# Stepper_Driver_jig_bottom.net
KiCad netlist of a schematic drawn in EAGLE
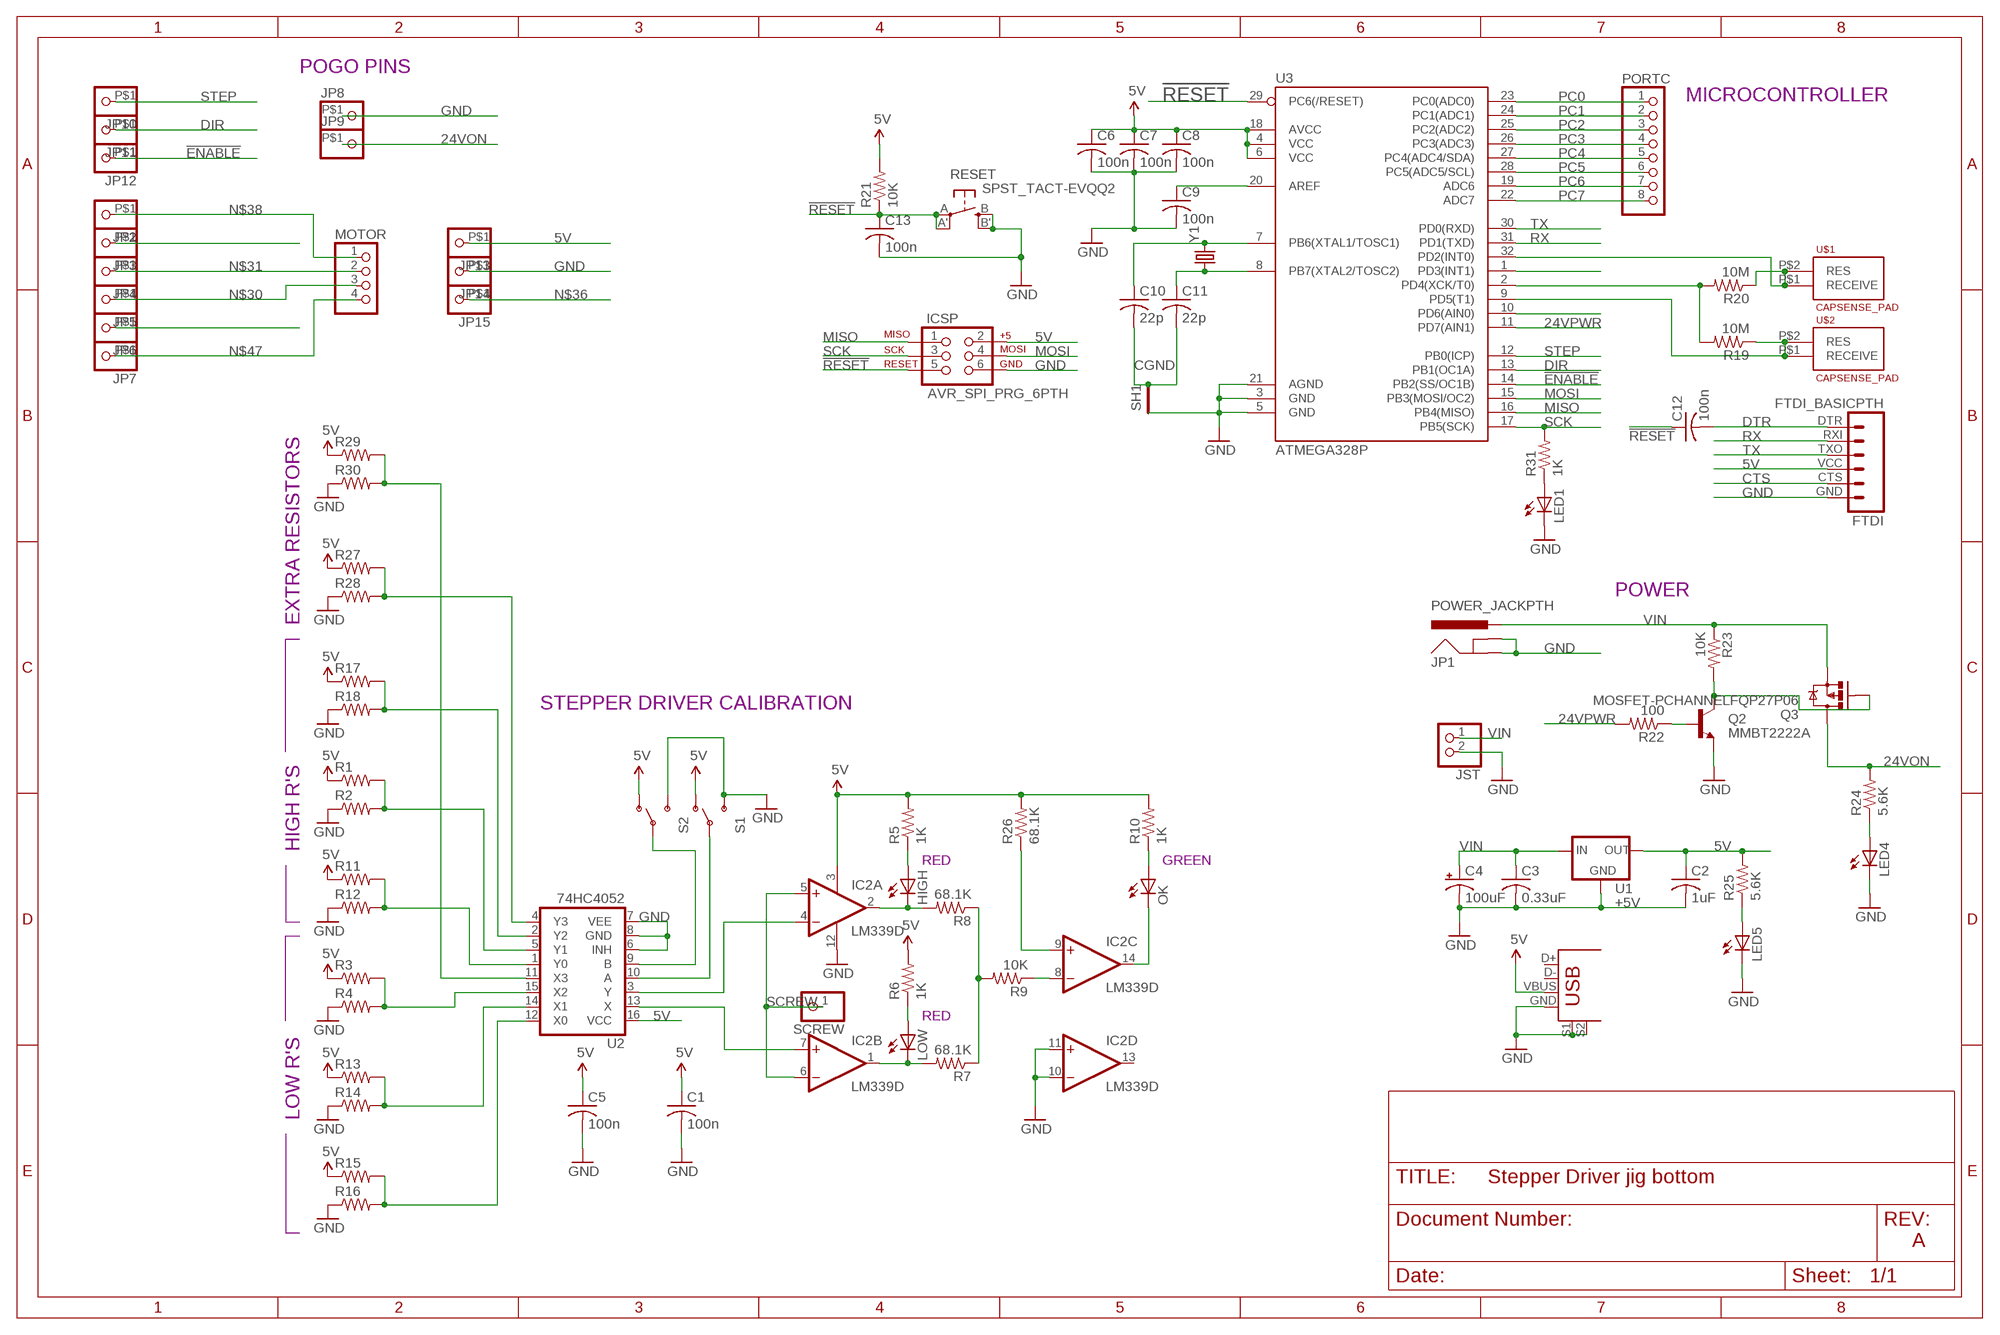
[diagram p0: schematic, sheet 1]

(export (version "E")
  (design (tool "Eeschema 10.0.6"))
  (components
    (comp (ref "C1")
      (value "100n")
      (footprint "eagle-import:C0805")
      (libsource (lib "eagle-import") (part "C-USC0805"))
    )
    (comp (ref "C2")
      (value "1uF")
      (footprint "eagle-import:C0805")
      (libsource (lib "eagle-import") (part "C-USC0805"))
    )
    (comp (ref "C3")
      (value "0.33uF")
      (footprint "eagle-import:C0805")
      (libsource (lib "eagle-import") (part "C-USC0805"))
    )
    (comp (ref "C4")
      (value "100uF")
      (footprint "eagle-import:UD-8X10_NICHICON")
      (libsource (lib "eagle-import") (part "CPOL-USUD-8X10"))
    )
    (comp (ref "C5")
      (value "100n")
      (footprint "eagle-import:C0805")
      (libsource (lib "eagle-import") (part "C-USC0805"))
    )
    (comp (ref "C6")
      (value "100n")
      (footprint "eagle-import:C0805")
      (libsource (lib "eagle-import") (part "C-USC0805"))
    )
    (comp (ref "C7")
      (value "100n")
      (footprint "eagle-import:C0805")
      (libsource (lib "eagle-import") (part "C-USC0805"))
    )
    (comp (ref "C8")
      (value "100n")
      (footprint "eagle-import:C0805")
      (libsource (lib "eagle-import") (part "C-USC0805"))
    )
    (comp (ref "C9")
      (value "100n")
      (footprint "eagle-import:C0805")
      (libsource (lib "eagle-import") (part "C-USC0805"))
    )
    (comp (ref "C10")
      (value "22p")
      (footprint "eagle-import:C0805")
      (libsource (lib "eagle-import") (part "C-USC0805"))
    )
    (comp (ref "C11")
      (value "22p")
      (footprint "eagle-import:C0805")
      (libsource (lib "eagle-import") (part "C-USC0805"))
    )
    (comp (ref "C12")
      (value "100n")
      (footprint "eagle-import:C0805")
      (libsource (lib "eagle-import") (part "C-USC0805"))
    )
    (comp (ref "C13")
      (value "100n")
      (footprint "eagle-import:C0805")
      (libsource (lib "eagle-import") (part "C-USC0805"))
    )
    (comp (ref "FTDI")
      (value "FTDI_BASICPTH")
      (footprint "eagle-import:FTDI_BASIC")
      (libsource (lib "eagle-import") (part "FTDI_BASICPTH"))
    )
    (comp (ref "HIGH")
      (value "LEDCHIPLED_1206")
      (footprint "eagle-import:CHIPLED_1206")
      (libsource (lib "eagle-import") (part "LEDCHIPLED_1206"))
    )
    (comp (ref "IC2")
      (value "LM339D")
      (footprint "eagle-import:SO14")
      (libsource (lib "eagle-import") (part "LM339D"))
    )
    (comp (ref "ICSP")
      (value "AVR_SPI_PRG_6PTH")
      (footprint "eagle-import:2X3")
      (libsource (lib "eagle-import") (part "AVR_SPI_PRG_6PTH"))
    )
    (comp (ref "JP1")
      (value "POWER_JACKPTH")
      (footprint "eagle-import:POWER_JACK_PTH")
      (libsource (lib "eagle-import") (part "POWER_JACKPTH"))
    )
    (comp (ref "JP2")
      (value "PINHD-1X1")
      (footprint "eagle-import:POGOPIN")
      (libsource (lib "eagle-import") (part "PINHD-1X1"))
    )
    (comp (ref "JP3")
      (value "PINHD-1X1")
      (footprint "eagle-import:POGOPIN")
      (libsource (lib "eagle-import") (part "PINHD-1X1"))
    )
    (comp (ref "JP4")
      (value "PINHD-1X1")
      (footprint "eagle-import:POGOPIN")
      (libsource (lib "eagle-import") (part "PINHD-1X1"))
    )
    (comp (ref "JP5")
      (value "PINHD-1X1")
      (footprint "eagle-import:POGOPIN")
      (libsource (lib "eagle-import") (part "PINHD-1X1"))
    )
    (comp (ref "JP6")
      (value "PINHD-1X1")
      (footprint "eagle-import:POGOPIN")
      (libsource (lib "eagle-import") (part "PINHD-1X1"))
    )
    (comp (ref "JP7")
      (value "PINHD-1X1")
      (footprint "eagle-import:POGOPIN")
      (libsource (lib "eagle-import") (part "PINHD-1X1"))
    )
    (comp (ref "JP8")
      (value "PINHD-1X1")
      (footprint "eagle-import:POGOPIN")
      (libsource (lib "eagle-import") (part "PINHD-1X1"))
    )
    (comp (ref "JP9")
      (value "PINHD-1X1")
      (footprint "eagle-import:POGOPIN")
      (libsource (lib "eagle-import") (part "PINHD-1X1"))
    )
    (comp (ref "JP10")
      (value "PINHD-1X1")
      (footprint "eagle-import:POGOPIN")
      (libsource (lib "eagle-import") (part "PINHD-1X1"))
    )
    (comp (ref "JP11")
      (value "PINHD-1X1")
      (footprint "eagle-import:POGOPIN")
      (libsource (lib "eagle-import") (part "PINHD-1X1"))
    )
    (comp (ref "JP12")
      (value "PINHD-1X1")
      (footprint "eagle-import:POGOPIN")
      (libsource (lib "eagle-import") (part "PINHD-1X1"))
    )
    (comp (ref "JP13")
      (value "PINHD-1X1")
      (footprint "eagle-import:POGOPIN")
      (libsource (lib "eagle-import") (part "PINHD-1X1"))
    )
    (comp (ref "JP14")
      (value "PINHD-1X1")
      (footprint "eagle-import:POGOPIN")
      (libsource (lib "eagle-import") (part "PINHD-1X1"))
    )
    (comp (ref "JP15")
      (value "PINHD-1X1")
      (footprint "eagle-import:POGOPIN")
      (libsource (lib "eagle-import") (part "PINHD-1X1"))
    )
    (comp (ref "JST")
      (value "JST_2PIN-SMT-RA")
      (footprint "eagle-import:JST-PH-2-SMT-RA")
      (libsource (lib "eagle-import") (part "JST_2PIN-SMT-RA"))
    )
    (comp (ref "LED1")
      (value "LEDCHIP-LED0805")
      (footprint "eagle-import:CHIP-LED0805")
      (libsource (lib "eagle-import") (part "LEDCHIP-LED0805"))
    )
    (comp (ref "LED4")
      (value "LEDCHIPLED_0805")
      (footprint "eagle-import:CHIPLED_0805")
      (libsource (lib "eagle-import") (part "LEDCHIPLED_0805"))
    )
    (comp (ref "LED5")
      (value "LEDCHIPLED_0805")
      (footprint "eagle-import:CHIPLED_0805")
      (libsource (lib "eagle-import") (part "LEDCHIPLED_0805"))
    )
    (comp (ref "LOW")
      (value "LEDCHIPLED_1206")
      (footprint "eagle-import:CHIPLED_1206")
      (libsource (lib "eagle-import") (part "LEDCHIPLED_1206"))
    )
    (comp (ref "MOTOR")
      (value "PINHD-1X4")
      (footprint "eagle-import:1X04")
      (libsource (lib "eagle-import") (part "PINHD-1X4"))
    )
    (comp (ref "OK")
      (value "LEDCHIPLED_1206")
      (footprint "eagle-import:CHIPLED_1206")
      (libsource (lib "eagle-import") (part "LEDCHIPLED_1206"))
    )
    (comp (ref "PORTC")
      (value "PINHD-1X8")
      (footprint "eagle-import:1X08")
      (libsource (lib "eagle-import") (part "PINHD-1X8"))
    )
    (comp (ref "Q2")
      (value "MMBT2222A")
      (footprint "eagle-import:SOT23-3")
      (libsource (lib "eagle-import") (part "TRANSISTOR_NPNMMBT2222A"))
    )
    (comp (ref "Q3")
      (value "MOSFET-PCHANNELFQP27P06")
      (footprint "eagle-import:TO220V")
      (libsource (lib "eagle-import") (part "MOSFET-PCHANNELFQP27P06"))
    )
    (comp (ref "R1")
      (value "R-US_M0805")
      (footprint "eagle-import:M0805")
      (libsource (lib "eagle-import") (part "R-US_M0805"))
    )
    (comp (ref "R2")
      (value "R-US_M0805")
      (footprint "eagle-import:M0805")
      (libsource (lib "eagle-import") (part "R-US_M0805"))
    )
    (comp (ref "R3")
      (value "R-US_M0805")
      (footprint "eagle-import:M0805")
      (libsource (lib "eagle-import") (part "R-US_M0805"))
    )
    (comp (ref "R4")
      (value "R-US_M0805")
      (footprint "eagle-import:M0805")
      (libsource (lib "eagle-import") (part "R-US_M0805"))
    )
    (comp (ref "R5")
      (value "1K")
      (footprint "eagle-import:M0805")
      (libsource (lib "eagle-import") (part "R-US_M0805"))
    )
    (comp (ref "R6")
      (value "1K")
      (footprint "eagle-import:M0805")
      (libsource (lib "eagle-import") (part "R-US_M0805"))
    )
    (comp (ref "R7")
      (value "68.1K")
      (footprint "eagle-import:M0805")
      (libsource (lib "eagle-import") (part "R-US_M0805"))
    )
    (comp (ref "R8")
      (value "68.1K")
      (footprint "eagle-import:M0805")
      (libsource (lib "eagle-import") (part "R-US_M0805"))
    )
    (comp (ref "R9")
      (value "10K")
      (footprint "eagle-import:M0805")
      (libsource (lib "eagle-import") (part "R-US_M0805"))
    )
    (comp (ref "R10")
      (value "1K")
      (footprint "eagle-import:M0805")
      (libsource (lib "eagle-import") (part "R-US_M0805"))
    )
    (comp (ref "R11")
      (value "R-US_M0805")
      (footprint "eagle-import:M0805")
      (libsource (lib "eagle-import") (part "R-US_M0805"))
    )
    (comp (ref "R12")
      (value "R-US_M0805")
      (footprint "eagle-import:M0805")
      (libsource (lib "eagle-import") (part "R-US_M0805"))
    )
    (comp (ref "R13")
      (value "R-US_M0805")
      (footprint "eagle-import:M0805")
      (libsource (lib "eagle-import") (part "R-US_M0805"))
    )
    (comp (ref "R14")
      (value "R-US_M0805")
      (footprint "eagle-import:M0805")
      (libsource (lib "eagle-import") (part "R-US_M0805"))
    )
    (comp (ref "R15")
      (value "R-US_M0805")
      (footprint "eagle-import:M0805")
      (libsource (lib "eagle-import") (part "R-US_M0805"))
    )
    (comp (ref "R16")
      (value "R-US_M0805")
      (footprint "eagle-import:M0805")
      (libsource (lib "eagle-import") (part "R-US_M0805"))
    )
    (comp (ref "R17")
      (value "R-US_M0805")
      (footprint "eagle-import:M0805")
      (libsource (lib "eagle-import") (part "R-US_M0805"))
    )
    (comp (ref "R18")
      (value "R-US_M0805")
      (footprint "eagle-import:M0805")
      (libsource (lib "eagle-import") (part "R-US_M0805"))
    )
    (comp (ref "R19")
      (value "10M")
      (footprint "eagle-import:M0805")
      (libsource (lib "eagle-import") (part "R-US_M0805"))
    )
    (comp (ref "R20")
      (value "10M")
      (footprint "eagle-import:M0805")
      (libsource (lib "eagle-import") (part "R-US_M0805"))
    )
    (comp (ref "R21")
      (value "10K")
      (footprint "eagle-import:M0805")
      (libsource (lib "eagle-import") (part "R-US_M0805"))
    )
    (comp (ref "R22")
      (value "100")
      (footprint "eagle-import:M0805")
      (libsource (lib "eagle-import") (part "R-US_M0805"))
    )
    (comp (ref "R23")
      (value "10K")
      (footprint "eagle-import:M0805")
      (libsource (lib "eagle-import") (part "R-US_M0805"))
    )
    (comp (ref "R24")
      (value "5.6K")
      (footprint "eagle-import:M0805")
      (libsource (lib "eagle-import") (part "R-US_M0805"))
    )
    (comp (ref "R25")
      (value "5.6K")
      (footprint "eagle-import:M0805")
      (libsource (lib "eagle-import") (part "R-US_M0805"))
    )
    (comp (ref "R26")
      (value "68.1K")
      (footprint "eagle-import:M0805")
      (libsource (lib "eagle-import") (part "R-US_M0805"))
    )
    (comp (ref "R27")
      (value "R-US_M0805")
      (footprint "eagle-import:M0805")
      (libsource (lib "eagle-import") (part "R-US_M0805"))
    )
    (comp (ref "R28")
      (value "R-US_M0805")
      (footprint "eagle-import:M0805")
      (libsource (lib "eagle-import") (part "R-US_M0805"))
    )
    (comp (ref "R29")
      (value "R-US_M0805")
      (footprint "eagle-import:M0805")
      (libsource (lib "eagle-import") (part "R-US_M0805"))
    )
    (comp (ref "R30")
      (value "R-US_M0805")
      (footprint "eagle-import:M0805")
      (libsource (lib "eagle-import") (part "R-US_M0805"))
    )
    (comp (ref "R31")
      (value "1K")
      (footprint "eagle-import:M0805")
      (libsource (lib "eagle-import") (part "R-US_M0805"))
    )
    (comp (ref "RESET")
      (value "SPST_TACT-EVQQ2")
      (footprint "eagle-import:EVQ-Q2")
      (libsource (lib "eagle-import") (part "SPST_TACT-EVQQ2"))
    )
    (comp (ref "S1")
      (value "SWITCH-SPDTKIT")
      (footprint "eagle-import:SWITCH-SPDT_KIT")
      (libsource (lib "eagle-import") (part "SWITCH-SPDTKIT"))
    )
    (comp (ref "S2")
      (value "SWITCH-SPDTKIT")
      (footprint "eagle-import:SWITCH-SPDT_KIT")
      (libsource (lib "eagle-import") (part "SWITCH-SPDTKIT"))
    )
    (comp (ref "SCREW")
      (value "PINHD-1X1")
      (footprint "eagle-import:1X01")
      (libsource (lib "eagle-import") (part "pinhead_PINHD-1X1"))
    )
    (comp (ref "SH1")
      (value "SHORTT5")
      (footprint "eagle-import:SHORT_TOP-50")
      (libsource (lib "eagle-import") (part "SHORTT5"))
    )
    (comp (ref "U$1")
      (value "CAPSENSE_PAD")
      (footprint "eagle-import:CAPSENSE_PAD")
      (libsource (lib "eagle-import") (part "CAPSENSE_PAD"))
    )
    (comp (ref "U$2")
      (value "CAPSENSE_PAD")
      (footprint "eagle-import:CAPSENSE_PAD")
      (libsource (lib "eagle-import") (part "CAPSENSE_PAD"))
    )
    (comp (ref "U$3")
      (value "USB+SHIELD")
      (footprint "eagle-import:USB-B-PTH")
      (libsource (lib "eagle-import") (part "USB+SHIELD"))
    )
    (comp (ref "U1")
      (value "+5V")
      (footprint "eagle-import:TO-252")
      (libsource (lib "eagle-import") (part "V_REG_78XX7812"))
    )
    (comp (ref "U2")
      (value "74HC4052")
      (footprint "eagle-import:SO16")
      (libsource (lib "eagle-import") (part "74HC4052SO"))
    )
    (comp (ref "U3")
      (value "ATMEGA328P")
      (footprint "eagle-import:TQFP32-08")
      (libsource (lib "eagle-import") (part "ATMEGA328P_TQFP"))
    )
    (comp (ref "Y1")
      (value "CRYSTALHC49US")
      (footprint "eagle-import:HC49US")
      (libsource (lib "eagle-import") (part "CRYSTALHC49US"))
    )
  )
  (nets
    (net (code "1") (name "/24VON") (class "Default")
      (node (ref "JP9") (pin "P$1") (pinfunction "1_P$1") (pintype "passive"))
      (node (ref "Q3") (pin "2") (pinfunction "D_2") (pintype "passive"))
      (node (ref "R24") (pin "2") (pinfunction "2_2") (pintype "passive"))
    )
    (net (code "2") (name "/24VPWR") (class "Default")
      (node (ref "R22") (pin "2") (pinfunction "2_2") (pintype "passive"))
      (node (ref "U3") (pin "11") (pinfunction "PD7(AIN1)_11") (pintype "bidirectional"))
    )
    (net (code "3") (name "/CGND") (class "Default")
      (node (ref "C10") (pin "2") (pinfunction "2_2") (pintype "passive"))
      (node (ref "C11") (pin "2") (pinfunction "2_2") (pintype "passive"))
      (node (ref "SH1") (pin "2") (pinfunction "P$2_2") (pintype "bidirectional"))
    )
    (net (code "4") (name "/CTS") (class "Default")
      (node (ref "FTDI") (pin "CTS") (pinfunction "5_CTS") (pintype "passive"))
    )
    (net (code "5") (name "/DIR") (class "Default")
      (node (ref "JP11") (pin "P$1") (pinfunction "1_P$1") (pintype "passive"))
      (node (ref "U3") (pin "13") (pinfunction "PB1(OC1A)_13") (pintype "bidirectional"))
    )
    (net (code "6") (name "/DTR") (class "Default")
      (node (ref "C12") (pin "2") (pinfunction "2_2") (pintype "passive"))
      (node (ref "FTDI") (pin "DTR") (pinfunction "1_DTR") (pintype "passive"))
    )
    (net (code "7") (name "/MISO") (class "Default")
      (node (ref "ICSP") (pin "1") (pinfunction "1_1") (pintype "passive"))
      (node (ref "U3") (pin "16") (pinfunction "PB4(MISO)_16") (pintype "bidirectional"))
    )
    (net (code "8") (name "/MOSI") (class "Default")
      (node (ref "ICSP") (pin "4") (pinfunction "4_4") (pintype "passive"))
      (node (ref "U3") (pin "15") (pinfunction "PB3(MOSI/OC2)_15") (pintype "bidirectional"))
    )
    (net (code "9") (name "/N$30") (class "Default")
      (node (ref "JP5") (pin "P$1") (pinfunction "1_P$1") (pintype "passive"))
      (node (ref "MOTOR") (pin "3") (pinfunction "3_3") (pintype "passive"))
    )
    (net (code "10") (name "/N$31") (class "Default")
      (node (ref "JP4") (pin "P$1") (pinfunction "1_P$1") (pintype "passive"))
      (node (ref "MOTOR") (pin "2") (pinfunction "2_2") (pintype "passive"))
    )
    (net (code "11") (name "/N$36") (class "Default")
      (node (ref "JP15") (pin "P$1") (pinfunction "1_P$1") (pintype "passive"))
    )
    (net (code "12") (name "/N$38") (class "Default")
      (node (ref "JP2") (pin "P$1") (pinfunction "1_P$1") (pintype "passive"))
      (node (ref "MOTOR") (pin "1") (pinfunction "1_1") (pintype "passive"))
    )
    (net (code "13") (name "/N$47") (class "Default")
      (node (ref "JP7") (pin "P$1") (pinfunction "1_P$1") (pintype "passive"))
      (node (ref "MOTOR") (pin "4") (pinfunction "4_4") (pintype "passive"))
    )
    (net (code "14") (name "/PC0") (class "Default")
      (node (ref "PORTC") (pin "1") (pinfunction "1_1") (pintype "passive"))
      (node (ref "U3") (pin "23") (pinfunction "PC0(ADC0)_23") (pintype "bidirectional"))
    )
    (net (code "15") (name "/PC1") (class "Default")
      (node (ref "PORTC") (pin "2") (pinfunction "2_2") (pintype "passive"))
      (node (ref "U3") (pin "24") (pinfunction "PC1(ADC1)_24") (pintype "bidirectional"))
    )
    (net (code "16") (name "/PC2") (class "Default")
      (node (ref "PORTC") (pin "3") (pinfunction "3_3") (pintype "passive"))
      (node (ref "U3") (pin "25") (pinfunction "PC2(ADC2)_25") (pintype "bidirectional"))
    )
    (net (code "17") (name "/PC3") (class "Default")
      (node (ref "PORTC") (pin "4") (pinfunction "4_4") (pintype "passive"))
      (node (ref "U3") (pin "26") (pinfunction "PC3(ADC3)_26") (pintype "bidirectional"))
    )
    (net (code "18") (name "/PC4") (class "Default")
      (node (ref "PORTC") (pin "5") (pinfunction "5_5") (pintype "passive"))
      (node (ref "U3") (pin "27") (pinfunction "PC4(ADC4/SDA)_27") (pintype "bidirectional"))
    )
    (net (code "19") (name "/PC5") (class "Default")
      (node (ref "PORTC") (pin "6") (pinfunction "6_6") (pintype "passive"))
      (node (ref "U3") (pin "28") (pinfunction "PC5(ADC5/SCL)_28") (pintype "bidirectional"))
    )
    (net (code "20") (name "/PC6") (class "Default")
      (node (ref "PORTC") (pin "7") (pinfunction "7_7") (pintype "passive"))
      (node (ref "U3") (pin "19") (pinfunction "ADC6_19") (pintype "bidirectional"))
    )
    (net (code "21") (name "/PC7") (class "Default")
      (node (ref "PORTC") (pin "8") (pinfunction "8_8") (pintype "passive"))
      (node (ref "U3") (pin "22") (pinfunction "ADC7_22") (pintype "bidirectional"))
    )
    (net (code "22") (name "/RX") (class "Default")
      (node (ref "FTDI") (pin "RXI") (pinfunction "2_RXI") (pintype "passive"))
      (node (ref "U3") (pin "31") (pinfunction "PD1(TXD)_31") (pintype "bidirectional"))
    )
    (net (code "23") (name "/SCK") (class "Default")
      (node (ref "ICSP") (pin "3") (pinfunction "3_3") (pintype "passive"))
      (node (ref "R31") (pin "2") (pinfunction "2_2") (pintype "passive"))
      (node (ref "U3") (pin "17") (pinfunction "PB5(SCK)_17") (pintype "bidirectional"))
    )
    (net (code "24") (name "/SCREW") (class "Default")
      (node (ref "IC2") (pin "5") (pinfunction "+IN_5") (pintype "input"))
      (node (ref "IC2") (pin "6") (pinfunction "-IN_6") (pintype "input"))
      (node (ref "SCREW") (pin "1") (pinfunction "1_1") (pintype "passive"))
    )
    (net (code "25") (name "/STEP") (class "Default")
      (node (ref "JP10") (pin "P$1") (pinfunction "1_P$1") (pintype "passive"))
      (node (ref "U3") (pin "12") (pinfunction "PB0(ICP)_12") (pintype "bidirectional"))
    )
    (net (code "26") (name "/TX") (class "Default")
      (node (ref "FTDI") (pin "TXO") (pinfunction "3_TXO") (pintype "passive"))
      (node (ref "U3") (pin "30") (pinfunction "PD0(RXD)_30") (pintype "bidirectional"))
    )
    (net (code "27") (name "/VIN") (class "Default")
      (node (ref "C3") (pin "1") (pinfunction "1_1") (pintype "passive"))
      (node (ref "C4") (pin "+") (pinfunction "+_+") (pintype "passive"))
      (node (ref "JP1") (pin "PWR") (pinfunction "PWR_PWR") (pintype "bidirectional"))
      (node (ref "JST") (pin "1") (pinfunction "2_1") (pintype "passive"))
      (node (ref "Q3") (pin "3") (pinfunction "S_3") (pintype "passive"))
      (node (ref "R23") (pin "1") (pinfunction "1_1") (pintype "passive"))
      (node (ref "U1") (pin "1") (pinfunction "IN_1") (pintype "input"))
    )
    (net (code "28") (name "/~{ENABLE}") (class "Default")
      (node (ref "JP12") (pin "P$1") (pinfunction "1_P$1") (pintype "passive"))
      (node (ref "U3") (pin "14") (pinfunction "PB2(SS/OC1B)_14") (pintype "bidirectional"))
    )
    (net (code "29") (name "/~{RESET}") (class "Default")
      (node (ref "C12") (pin "1") (pinfunction "1_1") (pintype "passive"))
      (node (ref "C13") (pin "1") (pinfunction "1_1") (pintype "passive"))
      (node (ref "ICSP") (pin "5") (pinfunction "5_5") (pintype "passive"))
      (node (ref "R21") (pin "1") (pinfunction "1_1") (pintype "passive"))
      (node (ref "RESET") (pin "A") (pinfunction "P_A") (pintype "passive"))
      (node (ref "RESET") (pin "A'") (pinfunction "P1_A'") (pintype "passive"))
      (node (ref "U3") (pin "29") (pinfunction "PC6(/RESET)_29") (pintype "bidirectional"))
    )
    (net (code "30") (name "5V") (class "Default")
      (node (ref "C1") (pin "1") (pinfunction "1_1") (pintype "passive"))
      (node (ref "C2") (pin "1") (pinfunction "1_1") (pintype "passive"))
      (node (ref "C5") (pin "1") (pinfunction "1_1") (pintype "passive"))
      (node (ref "C6") (pin "1") (pinfunction "1_1") (pintype "passive"))
      (node (ref "C7") (pin "1") (pinfunction "1_1") (pintype "passive"))
      (node (ref "C8") (pin "1") (pinfunction "1_1") (pintype "passive"))
      (node (ref "FTDI") (pin "VCC") (pinfunction "4_VCC") (pintype "passive"))
      (node (ref "IC2") (pin "3") (pinfunction "V+_3") (pintype "power_in"))
      (node (ref "ICSP") (pin "2") (pinfunction "2_2") (pintype "passive"))
      (node (ref "JP13") (pin "P$1") (pinfunction "1_P$1") (pintype "passive"))
      (node (ref "R1") (pin "1") (pinfunction "1_1") (pintype "passive"))
      (node (ref "R10") (pin "2") (pinfunction "2_2") (pintype "passive"))
      (node (ref "R11") (pin "1") (pinfunction "1_1") (pintype "passive"))
      (node (ref "R13") (pin "1") (pinfunction "1_1") (pintype "passive"))
      (node (ref "R15") (pin "1") (pinfunction "1_1") (pintype "passive"))
      (node (ref "R17") (pin "1") (pinfunction "1_1") (pintype "passive"))
      (node (ref "R21") (pin "2") (pinfunction "2_2") (pintype "passive"))
      (node (ref "R25") (pin "2") (pinfunction "2_2") (pintype "passive"))
      (node (ref "R26") (pin "2") (pinfunction "2_2") (pintype "passive"))
      (node (ref "R27") (pin "1") (pinfunction "1_1") (pintype "passive"))
      (node (ref "R29") (pin "1") (pinfunction "1_1") (pintype "passive"))
      (node (ref "R3") (pin "1") (pinfunction "1_1") (pintype "passive"))
      (node (ref "R5") (pin "2") (pinfunction "2_2") (pintype "passive"))
      (node (ref "R6") (pin "2") (pinfunction "2_2") (pintype "passive"))
      (node (ref "S1") (pin "1") (pinfunction "O_1") (pintype "passive"))
      (node (ref "S2") (pin "1") (pinfunction "O_1") (pintype "passive"))
      (node (ref "U$3") (pin "VBUS") (pinfunction "VBUS_VBUS") (pintype "bidirectional"))
      (node (ref "U1") (pin "2") (pinfunction "OUT_2") (pintype "passive"))
      (node (ref "U2") (pin "16") (pinfunction "VCC_16") (pintype "power_in"))
      (node (ref "U3") (pin "18") (pinfunction "AVCC_18") (pintype "bidirectional"))
      (node (ref "U3") (pin "4") (pinfunction "VCC_4") (pintype "bidirectional"))
      (node (ref "U3") (pin "6") (pinfunction "VCC_6") (pintype "bidirectional"))
    )
    (net (code "31") (name "GND") (class "Default")
      (node (ref "C1") (pin "2") (pinfunction "2_2") (pintype "passive"))
      (node (ref "C13") (pin "2") (pinfunction "2_2") (pintype "passive"))
      (node (ref "C2") (pin "2") (pinfunction "2_2") (pintype "passive"))
      (node (ref "C3") (pin "2") (pinfunction "2_2") (pintype "passive"))
      (node (ref "C4") (pin "-") (pinfunction "-_-") (pintype "passive"))
      (node (ref "C5") (pin "2") (pinfunction "2_2") (pintype "passive"))
      (node (ref "C6") (pin "2") (pinfunction "2_2") (pintype "passive"))
      (node (ref "C7") (pin "2") (pinfunction "2_2") (pintype "passive"))
      (node (ref "C8") (pin "2") (pinfunction "2_2") (pintype "passive"))
      (node (ref "C9") (pin "2") (pinfunction "2_2") (pintype "passive"))
      (node (ref "FTDI") (pin "GND") (pinfunction "6_GND") (pintype "passive"))
      (node (ref "IC2") (pin "10") (pinfunction "-IN_10") (pintype "input"))
      (node (ref "IC2") (pin "11") (pinfunction "+IN_11") (pintype "input"))
      (node (ref "IC2") (pin "12") (pinfunction "GND_12") (pintype "power_in"))
      (node (ref "ICSP") (pin "6") (pinfunction "6_6") (pintype "passive"))
      (node (ref "JP1") (pin "GND") (pinfunction "GND_GND") (pintype "bidirectional"))
      (node (ref "JP1") (pin "GNDBREAK") (pinfunction "GNDBREAK_GNDBREAK") (pintype "bidirectional"))
      (node (ref "JP14") (pin "P$1") (pinfunction "1_P$1") (pintype "passive"))
      (node (ref "JP8") (pin "P$1") (pinfunction "1_P$1") (pintype "passive"))
      (node (ref "JST") (pin "2") (pinfunction "1_2") (pintype "passive"))
      (node (ref "LED1") (pin "C") (pinfunction "C_C") (pintype "passive"))
      (node (ref "LED4") (pin "C") (pinfunction "C_C") (pintype "passive"))
      (node (ref "LED5") (pin "C") (pinfunction "C_C") (pintype "passive"))
      (node (ref "Q2") (pin "2") (pinfunction "E_2") (pintype "passive"))
      (node (ref "R12") (pin "1") (pinfunction "1_1") (pintype "passive"))
      (node (ref "R14") (pin "1") (pinfunction "1_1") (pintype "passive"))
      (node (ref "R16") (pin "1") (pinfunction "1_1") (pintype "passive"))
      (node (ref "R18") (pin "1") (pinfunction "1_1") (pintype "passive"))
      (node (ref "R2") (pin "1") (pinfunction "1_1") (pintype "passive"))
      (node (ref "R28") (pin "1") (pinfunction "1_1") (pintype "passive"))
      (node (ref "R30") (pin "1") (pinfunction "1_1") (pintype "passive"))
      (node (ref "R4") (pin "1") (pinfunction "1_1") (pintype "passive"))
      (node (ref "RESET") (pin "B") (pinfunction "S_B") (pintype "passive"))
      (node (ref "RESET") (pin "B'") (pinfunction "S1_B'") (pintype "passive"))
      (node (ref "S1") (pin "3") (pinfunction "S_3") (pintype "passive"))
      (node (ref "S2") (pin "3") (pinfunction "S_3") (pintype "passive"))
      (node (ref "SH1") (pin "1") (pinfunction "P$1_1") (pintype "bidirectional"))
      (node (ref "U$3") (pin "GND") (pinfunction "GND_GND") (pintype "bidirectional"))
      (node (ref "U$3") (pin "S1") (pinfunction "S1_S1") (pintype "bidirectional"))
      (node (ref "U$3") (pin "S2") (pinfunction "S2_S2") (pintype "bidirectional"))
      (node (ref "U1") (pin "3") (pinfunction "GND_3") (pintype "input"))
      (node (ref "U2") (pin "6") (pinfunction "INH_6") (pintype "input"))
      (node (ref "U2") (pin "7") (pinfunction "VEE_7") (pintype "power_in"))
      (node (ref "U2") (pin "8") (pinfunction "GND_8") (pintype "power_in"))
      (node (ref "U3") (pin "21") (pinfunction "AGND_21") (pintype "bidirectional"))
      (node (ref "U3") (pin "3") (pinfunction "GND_3") (pintype "bidirectional"))
      (node (ref "U3") (pin "5") (pinfunction "GND_5") (pintype "bidirectional"))
    )
    (net (code "32") (name "Net-(HIGH-PadA)") (class "Default")
      (node (ref "HIGH") (pin "A") (pinfunction "A_A") (pintype "passive"))
      (node (ref "R5") (pin "1") (pinfunction "1_1") (pintype "passive"))
    )
    (net (code "33") (name "Net-(IC2A--IN)") (class "Default")
      (node (ref "IC2") (pin "4") (pinfunction "-IN_4") (pintype "input"))
      (node (ref "U2") (pin "3") (pinfunction "Y_3") (pintype "bidirectional"))
    )
    (net (code "34") (name "Net-(IC2A-OUT)") (class "Default")
      (node (ref "HIGH") (pin "C") (pinfunction "C_C") (pintype "passive"))
      (node (ref "IC2") (pin "2") (pinfunction "OUT_2") (pintype "open_collector"))
      (node (ref "R8") (pin "2") (pinfunction "2_2") (pintype "passive"))
    )
    (net (code "35") (name "Net-(IC2B-+IN)") (class "Default")
      (node (ref "IC2") (pin "7") (pinfunction "+IN_7") (pintype "input"))
      (node (ref "U2") (pin "13") (pinfunction "X_13") (pintype "bidirectional"))
    )
    (net (code "36") (name "Net-(IC2B-OUT)") (class "Default")
      (node (ref "IC2") (pin "1") (pinfunction "OUT_1") (pintype "open_collector"))
      (node (ref "LOW") (pin "C") (pinfunction "C_C") (pintype "passive"))
      (node (ref "R7") (pin "2") (pinfunction "2_2") (pintype "passive"))
    )
    (net (code "37") (name "Net-(IC2C-+IN)") (class "Default")
      (node (ref "IC2") (pin "9") (pinfunction "+IN_9") (pintype "input"))
      (node (ref "R26") (pin "1") (pinfunction "1_1") (pintype "passive"))
    )
    (net (code "38") (name "Net-(IC2C--IN)") (class "Default")
      (node (ref "IC2") (pin "8") (pinfunction "-IN_8") (pintype "input"))
      (node (ref "R9") (pin "1") (pinfunction "1_1") (pintype "passive"))
    )
    (net (code "39") (name "Net-(IC2C-OUT)") (class "Default")
      (node (ref "IC2") (pin "14") (pinfunction "OUT_14") (pintype "open_collector"))
      (node (ref "OK") (pin "C") (pinfunction "C_C") (pintype "passive"))
    )
    (net (code "40") (name "Net-(LED1-PadA)") (class "Default")
      (node (ref "LED1") (pin "A") (pinfunction "A_A") (pintype "passive"))
      (node (ref "R31") (pin "1") (pinfunction "1_1") (pintype "passive"))
    )
    (net (code "41") (name "Net-(LED4-PadA)") (class "Default")
      (node (ref "LED4") (pin "A") (pinfunction "A_A") (pintype "passive"))
      (node (ref "R24") (pin "1") (pinfunction "1_1") (pintype "passive"))
    )
    (net (code "42") (name "Net-(LED5-PadA)") (class "Default")
      (node (ref "LED5") (pin "A") (pinfunction "A_A") (pintype "passive"))
      (node (ref "R25") (pin "1") (pinfunction "1_1") (pintype "passive"))
    )
    (net (code "43") (name "Net-(LOW-PadA)") (class "Default")
      (node (ref "LOW") (pin "A") (pinfunction "A_A") (pintype "passive"))
      (node (ref "R6") (pin "1") (pinfunction "1_1") (pintype "passive"))
    )
    (net (code "44") (name "Net-(OK-PadA)") (class "Default")
      (node (ref "OK") (pin "A") (pinfunction "A_A") (pintype "passive"))
      (node (ref "R10") (pin "1") (pinfunction "1_1") (pintype "passive"))
    )
    (net (code "45") (name "Net-(Q2-B)") (class "Default")
      (node (ref "Q2") (pin "1") (pinfunction "B_1") (pintype "passive"))
      (node (ref "R22") (pin "1") (pinfunction "1_1") (pintype "passive"))
    )
    (net (code "46") (name "Net-(Q2-C)") (class "Default")
      (node (ref "Q2") (pin "3") (pinfunction "C_3") (pintype "passive"))
      (node (ref "Q3") (pin "1") (pinfunction "G_1") (pintype "passive"))
      (node (ref "R23") (pin "2") (pinfunction "2_2") (pintype "passive"))
    )
    (net (code "47") (name "Net-(R7-Pad1)") (class "Default")
      (node (ref "R7") (pin "1") (pinfunction "1_1") (pintype "passive"))
      (node (ref "R8") (pin "1") (pinfunction "1_1") (pintype "passive"))
      (node (ref "R9") (pin "2") (pinfunction "2_2") (pintype "passive"))
    )
    (net (code "48") (name "Net-(S1-P)") (class "Default")
      (node (ref "S1") (pin "2") (pinfunction "P_2") (pintype "passive"))
      (node (ref "U2") (pin "10") (pinfunction "A_10") (pintype "input"))
    )
    (net (code "49") (name "Net-(S2-P)") (class "Default")
      (node (ref "S2") (pin "2") (pinfunction "P_2") (pintype "passive"))
      (node (ref "U2") (pin "9") (pinfunction "B_9") (pintype "input"))
    )
    (net (code "50") (name "Net-(U$1-RECEIVE)") (class "Default")
      (node (ref "R20") (pin "1") (pinfunction "1_1") (pintype "passive"))
      (node (ref "U$1") (pin "P$1") (pinfunction "RECEIVE_P$1") (pintype "bidirectional"))
      (node (ref "U$1") (pin "P$2") (pinfunction "RES_P$2") (pintype "bidirectional"))
      (node (ref "U3") (pin "32") (pinfunction "PD2(INT0)_32") (pintype "bidirectional"))
    )
    (net (code "51") (name "Net-(U$2-RECEIVE)") (class "Default")
      (node (ref "R19") (pin "1") (pinfunction "1_1") (pintype "passive"))
      (node (ref "U$2") (pin "P$1") (pinfunction "RECEIVE_P$1") (pintype "bidirectional"))
      (node (ref "U$2") (pin "P$2") (pinfunction "RES_P$2") (pintype "bidirectional"))
      (node (ref "U3") (pin "9") (pinfunction "PD5(T1)_9") (pintype "bidirectional"))
    )
    (net (code "52") (name "Net-(U2-X0)") (class "Default")
      (node (ref "R15") (pin "2") (pinfunction "2_2") (pintype "passive"))
      (node (ref "R16") (pin "2") (pinfunction "2_2") (pintype "passive"))
      (node (ref "U2") (pin "12") (pinfunction "X0_12") (pintype "bidirectional"))
    )
    (net (code "53") (name "Net-(U2-X1)") (class "Default")
      (node (ref "R13") (pin "2") (pinfunction "2_2") (pintype "passive"))
      (node (ref "R14") (pin "2") (pinfunction "2_2") (pintype "passive"))
      (node (ref "U2") (pin "14") (pinfunction "X1_14") (pintype "bidirectional"))
    )
    (net (code "54") (name "Net-(U2-X2)") (class "Default")
      (node (ref "R3") (pin "2") (pinfunction "2_2") (pintype "passive"))
      (node (ref "R4") (pin "2") (pinfunction "2_2") (pintype "passive"))
      (node (ref "U2") (pin "15") (pinfunction "X2_15") (pintype "bidirectional"))
    )
    (net (code "55") (name "Net-(U2-X3)") (class "Default")
      (node (ref "R29") (pin "2") (pinfunction "2_2") (pintype "passive"))
      (node (ref "R30") (pin "2") (pinfunction "2_2") (pintype "passive"))
      (node (ref "U2") (pin "11") (pinfunction "X3_11") (pintype "bidirectional"))
    )
    (net (code "56") (name "Net-(U2-Y0)") (class "Default")
      (node (ref "R11") (pin "2") (pinfunction "2_2") (pintype "passive"))
      (node (ref "R12") (pin "2") (pinfunction "2_2") (pintype "passive"))
      (node (ref "U2") (pin "1") (pinfunction "Y0_1") (pintype "bidirectional"))
    )
    (net (code "57") (name "Net-(U2-Y1)") (class "Default")
      (node (ref "R1") (pin "2") (pinfunction "2_2") (pintype "passive"))
      (node (ref "R2") (pin "2") (pinfunction "2_2") (pintype "passive"))
      (node (ref "U2") (pin "5") (pinfunction "Y1_5") (pintype "bidirectional"))
    )
    (net (code "58") (name "Net-(U2-Y2)") (class "Default")
      (node (ref "R17") (pin "2") (pinfunction "2_2") (pintype "passive"))
      (node (ref "R18") (pin "2") (pinfunction "2_2") (pintype "passive"))
      (node (ref "U2") (pin "2") (pinfunction "Y2_2") (pintype "bidirectional"))
    )
    (net (code "59") (name "Net-(U2-Y3)") (class "Default")
      (node (ref "R27") (pin "2") (pinfunction "2_2") (pintype "passive"))
      (node (ref "R28") (pin "2") (pinfunction "2_2") (pintype "passive"))
      (node (ref "U2") (pin "4") (pinfunction "Y3_4") (pintype "bidirectional"))
    )
    (net (code "60") (name "Net-(U3-AREF)") (class "Default")
      (node (ref "C9") (pin "1") (pinfunction "1_1") (pintype "passive"))
      (node (ref "U3") (pin "20") (pinfunction "AREF_20") (pintype "bidirectional"))
    )
    (net (code "61") (name "Net-(U3-PB6(XTAL1{slash}TOSC1))") (class "Default")
      (node (ref "C10") (pin "1") (pinfunction "1_1") (pintype "passive"))
      (node (ref "U3") (pin "7") (pinfunction "PB6(XTAL1/TOSC1)_7") (pintype "bidirectional"))
      (node (ref "Y1") (pin "2") (pinfunction "2_2") (pintype "passive"))
    )
    (net (code "62") (name "Net-(U3-PB7(XTAL2{slash}TOSC2))") (class "Default")
      (node (ref "C11") (pin "1") (pinfunction "1_1") (pintype "passive"))
      (node (ref "U3") (pin "8") (pinfunction "PB7(XTAL2/TOSC2)_8") (pintype "bidirectional"))
      (node (ref "Y1") (pin "1") (pinfunction "1_1") (pintype "passive"))
    )
    (net (code "63") (name "Net-(U3-PD4(XCK{slash}T0))") (class "Default")
      (node (ref "R19") (pin "2") (pinfunction "2_2") (pintype "passive"))
      (node (ref "R20") (pin "2") (pinfunction "2_2") (pintype "passive"))
      (node (ref "U3") (pin "2") (pinfunction "PD4(XCK/T0)_2") (pintype "bidirectional"))
    )
    (net (code "64") (name "unconnected-(IC2D-OUT-Pad13)") (class "Default")
      (node (ref "IC2") (pin "13") (pinfunction "OUT_13") (pintype "open_collector"))
    )
    (net (code "65") (name "unconnected-(JP3-1-PadP$1)") (class "Default")
      (node (ref "JP3") (pin "P$1") (pinfunction "1_P$1") (pintype "passive"))
    )
    (net (code "66") (name "unconnected-(JP6-1-PadP$1)") (class "Default")
      (node (ref "JP6") (pin "P$1") (pinfunction "1_P$1") (pintype "passive"))
    )
    (net (code "67") (name "unconnected-(U$3-PadD+)") (class "Default")
      (node (ref "U$3") (pin "D+") (pinfunction "D+_D+") (pintype "bidirectional"))
    )
    (net (code "68") (name "unconnected-(U$3-PadD-)") (class "Default")
      (node (ref "U$3") (pin "D-") (pinfunction "D-_D-") (pintype "bidirectional"))
    )
    (net (code "69") (name "unconnected-(U3-PD3(INT1)-Pad1)") (class "Default")
      (node (ref "U3") (pin "1") (pinfunction "PD3(INT1)_1") (pintype "bidirectional"))
    )
    (net (code "70") (name "unconnected-(U3-PD6(AIN0)-Pad10)") (class "Default")
      (node (ref "U3") (pin "10") (pinfunction "PD6(AIN0)_10") (pintype "bidirectional"))
    )
  )
)
